# Sheet1.net
KiCad netlist of a schematic drawn in Altium Designer
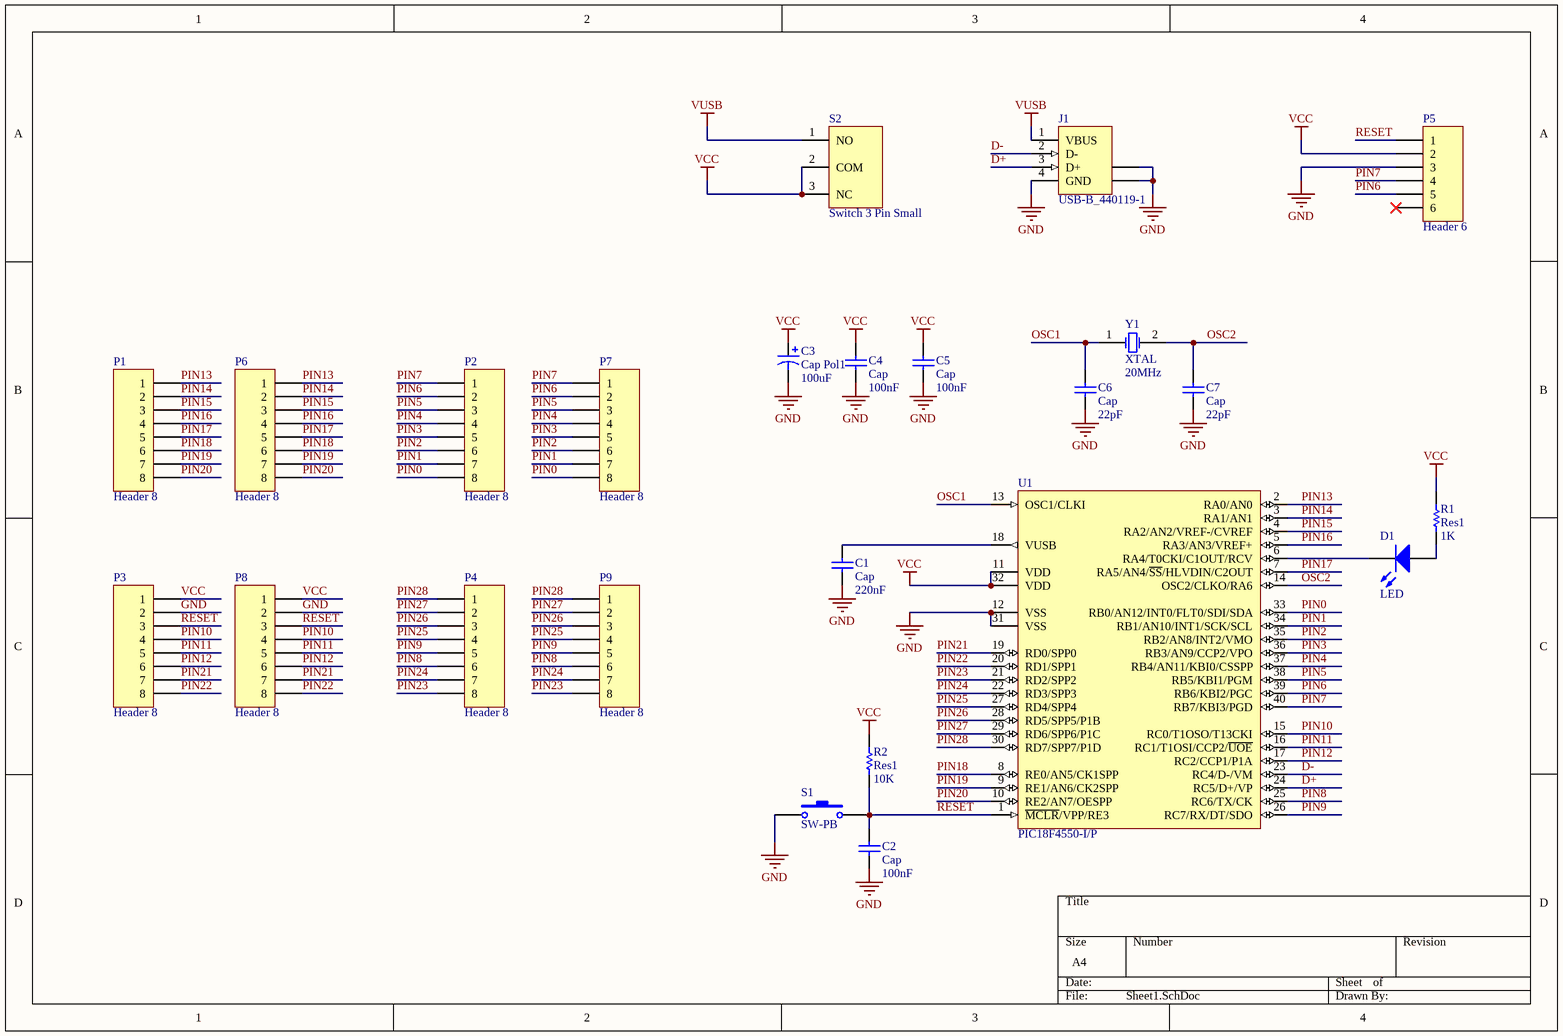
[diagram p0: Sheet1.SchDoc]

(export (version "E")
  (design (tool "Eeschema 10.0.6"))
  (components
    (comp (ref "C1")
      (value "Cap")
      (footprint "C1206")
      (description "Capacitor")
      (fields (field (name "ALTIUM_VALUE") "220nF") (field (name "PUBLISHER") "Altium Limited"))
      (libsource (lib "Miscellaneous Devices") (part "Cap"))
    )
    (comp (ref "C2")
      (value "Cap")
      (footprint "C1206")
      (description "Capacitor")
      (fields (field (name "ALTIUM_VALUE") "100nF") (field (name "PUBLISHER") "Altium Limited"))
      (libsource (lib "Miscellaneous Devices") (part "Cap"))
    )
    (comp (ref "C3")
      (value "Cap Pol1")
      (footprint "CAP1")
      (description "Polarized Capacitor (Radial)")
      (fields (field (name "ALTIUM_VALUE") "100uF") (field (name "PUBLISHER") "Altium Limited"))
      (libsource (lib "Miscellaneous Devices") (part "Cap Pol1"))
    )
    (comp (ref "C4")
      (value "Cap")
      (footprint "C1206")
      (description "Capacitor")
      (fields (field (name "ALTIUM_VALUE") "100nF") (field (name "PUBLISHER") "Altium Limited"))
      (libsource (lib "Miscellaneous Devices") (part "Cap"))
    )
    (comp (ref "C5")
      (value "Cap")
      (footprint "C1206")
      (description "Capacitor")
      (fields (field (name "ALTIUM_VALUE") "100nF") (field (name "PUBLISHER") "Altium Limited"))
      (libsource (lib "Miscellaneous Devices") (part "Cap"))
    )
    (comp (ref "C6")
      (value "Cap")
      (footprint "C1206")
      (description "Capacitor")
      (fields (field (name "ALTIUM_VALUE") "22pF") (field (name "PUBLISHER") "Altium Limited"))
      (libsource (lib "Miscellaneous Devices") (part "Cap"))
    )
    (comp (ref "C7")
      (value "Cap")
      (footprint "C1206")
      (description "Capacitor")
      (fields (field (name "ALTIUM_VALUE") "22pF") (field (name "PUBLISHER") "Altium Limited"))
      (libsource (lib "Miscellaneous Devices") (part "Cap"))
    )
    (comp (ref "D1")
      (value "LED")
      (footprint "LED0")
      (description "Typical RED GaAs LED")
      (fields (field (name "DESIGNER") "Meysam Parvizi") (field (name "EMAIL") "meysam.parvizi.ir@gmail.com"))
      (libsource (lib "mp") (part "LED"))
    )
    (comp (ref "J1")
      (value "USB-B_440119-1")
      (footprint "USB-B")
      (description "USB 1.1, Right Angle, Thru-Hole, B Type, Receptacle, 4 Position, Beige")
      (fields (field (name "PUBLISHER") "Altium Limited"))
      (libsource (lib "mp") (part "USB-B_440119-1"))
    )
    (comp (ref "P1")
      (value "Header 8")
      (footprint "HDR1X8")
      (description "Header, 8-Pin")
      (fields (field (name "PUBLISHER") "Altium Limited"))
      (libsource (lib "Miscellaneous Connectors") (part "Header 8"))
    )
    (comp (ref "P2")
      (value "Header 8")
      (footprint "HDR1X8")
      (description "Header, 8-Pin")
      (fields (field (name "PUBLISHER") "Altium Limited"))
      (libsource (lib "") (part "Header 8_1"))
    )
    (comp (ref "P3")
      (value "Header 8")
      (footprint "HDR1X8")
      (description "Header, 8-Pin")
      (fields (field (name "PUBLISHER") "Altium Limited"))
      (libsource (lib "Miscellaneous Connectors") (part "Header 8"))
    )
    (comp (ref "P4")
      (value "Header 8")
      (footprint "HDR1X8")
      (description "Header, 8-Pin")
      (fields (field (name "PUBLISHER") "Altium Limited"))
      (libsource (lib "") (part "Header 8_1"))
    )
    (comp (ref "P5")
      (value "Header 6")
      (footprint "HDR1X6")
      (description "Header, 6-Pin")
      (fields (field (name "PUBLISHER") "Altium Limited"))
      (libsource (lib "Miscellaneous Connectors") (part "Header 6"))
    )
    (comp (ref "P6")
      (value "Header 8")
      (footprint "HDR1X8")
      (description "Header, 8-Pin")
      (fields (field (name "PUBLISHER") "Altium Limited"))
      (libsource (lib "Miscellaneous Connectors") (part "Header 8"))
    )
    (comp (ref "P7")
      (value "Header 8")
      (footprint "HDR1X8")
      (description "Header, 8-Pin")
      (fields (field (name "PUBLISHER") "Altium Limited"))
      (libsource (lib "") (part "Header 8_1"))
    )
    (comp (ref "P8")
      (value "Header 8")
      (footprint "HDR1X8")
      (description "Header, 8-Pin")
      (fields (field (name "PUBLISHER") "Altium Limited"))
      (libsource (lib "Miscellaneous Connectors") (part "Header 8"))
    )
    (comp (ref "P9")
      (value "Header 8")
      (footprint "HDR1X8")
      (description "Header, 8-Pin")
      (fields (field (name "PUBLISHER") "Altium Limited"))
      (libsource (lib "") (part "Header 8_1"))
    )
    (comp (ref "R1")
      (value "Res1")
      (footprint "C1206")
      (description "Resistor")
      (fields (field (name "ALTIUM_VALUE") "1K") (field (name "PUBLISHER") "Altium Limited"))
      (libsource (lib "Miscellaneous Devices") (part "Res1"))
    )
    (comp (ref "R2")
      (value "Res1")
      (footprint "C1206")
      (description "Resistor")
      (fields (field (name "ALTIUM_VALUE") "10K") (field (name "PUBLISHER") "Altium Limited"))
      (libsource (lib "Miscellaneous Devices") (part "Res1"))
    )
    (comp (ref "S1")
      (value "SW-PB")
      (footprint "PUSH0")
      (description "Switch")
      (fields (field (name "PUBLISHER") "Altium Limited"))
      (libsource (lib "mp") (part "SW-PB"))
    )
    (comp (ref "S2")
      (value "Switch 3 Pin Small")
      (footprint "SW_ON_OFF_SMALL")
      (description "Switch 3 Pin")
      (fields (field (name "DESIGNER") "Meysam Parvizi") (field (name "EMAIL") "meysam.parvizi.ir@gmail.com"))
      (libsource (lib "mp") (part "Switch 3 Pin Small"))
    )
    (comp (ref "U1")
      (value "PIC18F4550-I/P")
      (footprint "PDIP600-P40")
      (fields (field (name "PUBLISHER") "Altium Limited"))
      (libsource (lib "Microchip Microcontroller 8-Bit PIC18") (part "PIC18F4550-I/P"))
    )
    (comp (ref "Y1")
      (value "XTAL")
      (footprint "XTAL")
      (description "Crystal Oscillator")
      (fields
        (field (name "ALTIUM_VALUE") "20MHz")
        (field (name "DESIGNER") "Meysam Parvizi")
        (field (name "EMAIL") "meysam.parvizi.ir@gmail.com")
      )
      (libsource (lib "mp") (part "XTAL"))
    )
  )
  (nets
    (net (code "1") (name "/D+") (class "Default")
      (node (ref "J1") (pin "3") (pinfunction "D+_3") (pintype "input"))
      (node (ref "U1") (pin "24") (pinfunction "RC5/D+/VP_24") (pintype "bidirectional"))
    )
    (net (code "2") (name "/D-") (class "Default")
      (node (ref "J1") (pin "2") (pinfunction "D-_2") (pintype "input"))
      (node (ref "U1") (pin "23") (pinfunction "RC4/D-/VM_23") (pintype "bidirectional"))
    )
    (net (code "3") (name "/OSC1") (class "Default")
      (node (ref "C6") (pin "2") (pinfunction "2_2") (pintype "passive"))
      (node (ref "U1") (pin "13") (pinfunction "OSC1/CLKI_13") (pintype "input"))
      (node (ref "Y1") (pin "1") (pinfunction "OSC1_1") (pintype "passive"))
    )
    (net (code "4") (name "/OSC2") (class "Default")
      (node (ref "C7") (pin "2") (pinfunction "2_2") (pintype "passive"))
      (node (ref "U1") (pin "14") (pinfunction "OSC2/CLKO/RA6_14") (pintype "bidirectional"))
      (node (ref "Y1") (pin "2") (pinfunction "OSC2_2") (pintype "passive"))
    )
    (net (code "5") (name "/PIN0") (class "Default")
      (node (ref "P2") (pin "8") (pinfunction "8_8") (pintype "passive"))
      (node (ref "P7") (pin "8") (pinfunction "8_8") (pintype "passive"))
      (node (ref "U1") (pin "33") (pinfunction "RB0/AN12/INT0/FLT0/SDI/SDA_33") (pintype "bidirectional"))
    )
    (net (code "6") (name "/PIN1") (class "Default")
      (node (ref "P2") (pin "7") (pinfunction "7_7") (pintype "passive"))
      (node (ref "P7") (pin "7") (pinfunction "7_7") (pintype "passive"))
      (node (ref "U1") (pin "34") (pinfunction "RB1/AN10/INT1/SCK/SCL_34") (pintype "bidirectional"))
    )
    (net (code "7") (name "/PIN2") (class "Default")
      (node (ref "P2") (pin "6") (pinfunction "6_6") (pintype "passive"))
      (node (ref "P7") (pin "6") (pinfunction "6_6") (pintype "passive"))
      (node (ref "U1") (pin "35") (pinfunction "RB2/AN8/INT2/VMO_35") (pintype "bidirectional"))
    )
    (net (code "8") (name "/PIN3") (class "Default")
      (node (ref "P2") (pin "5") (pinfunction "5_5") (pintype "passive"))
      (node (ref "P7") (pin "5") (pinfunction "5_5") (pintype "passive"))
      (node (ref "U1") (pin "36") (pinfunction "RB3/AN9/CCP2/VPO_36") (pintype "bidirectional"))
    )
    (net (code "9") (name "/PIN4") (class "Default")
      (node (ref "P2") (pin "4") (pinfunction "4_4") (pintype "passive"))
      (node (ref "P7") (pin "4") (pinfunction "4_4") (pintype "passive"))
      (node (ref "U1") (pin "37") (pinfunction "RB4/AN11/KBI0/CSSPP_37") (pintype "bidirectional"))
    )
    (net (code "10") (name "/PIN5") (class "Default")
      (node (ref "P2") (pin "3") (pinfunction "3_3") (pintype "passive"))
      (node (ref "P7") (pin "3") (pinfunction "3_3") (pintype "passive"))
      (node (ref "U1") (pin "38") (pinfunction "RB5/KBI1/PGM_38") (pintype "bidirectional"))
    )
    (net (code "11") (name "/PIN6") (class "Default")
      (node (ref "P2") (pin "2") (pinfunction "2_2") (pintype "passive"))
      (node (ref "P5") (pin "5") (pinfunction "5_5") (pintype "passive"))
      (node (ref "P7") (pin "2") (pinfunction "2_2") (pintype "passive"))
      (node (ref "U1") (pin "39") (pinfunction "RB6/KBI2/PGC_39") (pintype "bidirectional"))
    )
    (net (code "12") (name "/PIN7") (class "Default")
      (node (ref "P2") (pin "1") (pinfunction "1_1") (pintype "passive"))
      (node (ref "P5") (pin "4") (pinfunction "4_4") (pintype "passive"))
      (node (ref "P7") (pin "1") (pinfunction "1_1") (pintype "passive"))
      (node (ref "U1") (pin "40") (pinfunction "RB7/KBI3/PGD_40") (pintype "bidirectional"))
    )
    (net (code "13") (name "/PIN8") (class "Default")
      (node (ref "P4") (pin "6") (pinfunction "6_6") (pintype "passive"))
      (node (ref "P9") (pin "6") (pinfunction "6_6") (pintype "passive"))
      (node (ref "U1") (pin "25") (pinfunction "RC6/TX/CK_25") (pintype "bidirectional"))
    )
    (net (code "14") (name "/PIN9") (class "Default")
      (node (ref "P4") (pin "5") (pinfunction "5_5") (pintype "passive"))
      (node (ref "P9") (pin "5") (pinfunction "5_5") (pintype "passive"))
      (node (ref "U1") (pin "26") (pinfunction "RC7/RX/DT/SDO_26") (pintype "bidirectional"))
    )
    (net (code "15") (name "/PIN10") (class "Default")
      (node (ref "P3") (pin "4") (pinfunction "4_4") (pintype "passive"))
      (node (ref "P8") (pin "4") (pinfunction "4_4") (pintype "passive"))
      (node (ref "U1") (pin "15") (pinfunction "RC0/T1OSO/T13CKI_15") (pintype "bidirectional"))
    )
    (net (code "16") (name "/PIN11") (class "Default")
      (node (ref "P3") (pin "5") (pinfunction "5_5") (pintype "passive"))
      (node (ref "P8") (pin "5") (pinfunction "5_5") (pintype "passive"))
      (node (ref "U1") (pin "16") (pinfunction "RC1/T1OSI/CCP2/~{UOE}_16") (pintype "bidirectional"))
    )
    (net (code "17") (name "/PIN12") (class "Default")
      (node (ref "P3") (pin "6") (pinfunction "6_6") (pintype "passive"))
      (node (ref "P8") (pin "6") (pinfunction "6_6") (pintype "passive"))
      (node (ref "U1") (pin "17") (pinfunction "RC2/CCP1/P1A_17") (pintype "bidirectional"))
    )
    (net (code "18") (name "/PIN13") (class "Default")
      (node (ref "P1") (pin "1") (pinfunction "1_1") (pintype "passive"))
      (node (ref "P6") (pin "1") (pinfunction "1_1") (pintype "passive"))
      (node (ref "U1") (pin "2") (pinfunction "RA0/AN0_2") (pintype "bidirectional"))
    )
    (net (code "19") (name "/PIN14") (class "Default")
      (node (ref "P1") (pin "2") (pinfunction "2_2") (pintype "passive"))
      (node (ref "P6") (pin "2") (pinfunction "2_2") (pintype "passive"))
      (node (ref "U1") (pin "3") (pinfunction "RA1/AN1_3") (pintype "bidirectional"))
    )
    (net (code "20") (name "/PIN15") (class "Default")
      (node (ref "P1") (pin "3") (pinfunction "3_3") (pintype "passive"))
      (node (ref "P6") (pin "3") (pinfunction "3_3") (pintype "passive"))
      (node (ref "U1") (pin "4") (pinfunction "RA2/AN2/VREF-/CVREF_4") (pintype "bidirectional"))
    )
    (net (code "21") (name "/PIN16") (class "Default")
      (node (ref "P1") (pin "4") (pinfunction "4_4") (pintype "passive"))
      (node (ref "P6") (pin "4") (pinfunction "4_4") (pintype "passive"))
      (node (ref "U1") (pin "5") (pinfunction "RA3/AN3/VREF+_5") (pintype "bidirectional"))
    )
    (net (code "22") (name "/PIN17") (class "Default")
      (node (ref "P1") (pin "5") (pinfunction "5_5") (pintype "passive"))
      (node (ref "P6") (pin "5") (pinfunction "5_5") (pintype "passive"))
      (node (ref "U1") (pin "7") (pinfunction "RA5/AN4/~{SS}/HLVDIN/C2OUT_7") (pintype "bidirectional"))
    )
    (net (code "23") (name "/PIN18") (class "Default")
      (node (ref "P1") (pin "6") (pinfunction "6_6") (pintype "passive"))
      (node (ref "P6") (pin "6") (pinfunction "6_6") (pintype "passive"))
      (node (ref "U1") (pin "8") (pinfunction "RE0/AN5/CK1SPP_8") (pintype "bidirectional"))
    )
    (net (code "24") (name "/PIN19") (class "Default")
      (node (ref "P1") (pin "7") (pinfunction "7_7") (pintype "passive"))
      (node (ref "P6") (pin "7") (pinfunction "7_7") (pintype "passive"))
      (node (ref "U1") (pin "9") (pinfunction "RE1/AN6/CK2SPP_9") (pintype "bidirectional"))
    )
    (net (code "25") (name "/PIN20") (class "Default")
      (node (ref "P1") (pin "8") (pinfunction "8_8") (pintype "passive"))
      (node (ref "P6") (pin "8") (pinfunction "8_8") (pintype "passive"))
      (node (ref "U1") (pin "10") (pinfunction "RE2/AN7/OESPP_10") (pintype "bidirectional"))
    )
    (net (code "26") (name "/PIN21") (class "Default")
      (node (ref "P3") (pin "7") (pinfunction "7_7") (pintype "passive"))
      (node (ref "P8") (pin "7") (pinfunction "7_7") (pintype "passive"))
      (node (ref "U1") (pin "19") (pinfunction "RD0/SPP0_19") (pintype "bidirectional"))
    )
    (net (code "27") (name "/PIN22") (class "Default")
      (node (ref "P3") (pin "8") (pinfunction "8_8") (pintype "passive"))
      (node (ref "P8") (pin "8") (pinfunction "8_8") (pintype "passive"))
      (node (ref "U1") (pin "20") (pinfunction "RD1/SPP1_20") (pintype "bidirectional"))
    )
    (net (code "28") (name "/PIN23") (class "Default")
      (node (ref "P4") (pin "8") (pinfunction "8_8") (pintype "passive"))
      (node (ref "P9") (pin "8") (pinfunction "8_8") (pintype "passive"))
      (node (ref "U1") (pin "21") (pinfunction "RD2/SPP2_21") (pintype "bidirectional"))
    )
    (net (code "29") (name "/PIN24") (class "Default")
      (node (ref "P4") (pin "7") (pinfunction "7_7") (pintype "passive"))
      (node (ref "P9") (pin "7") (pinfunction "7_7") (pintype "passive"))
      (node (ref "U1") (pin "22") (pinfunction "RD3/SPP3_22") (pintype "bidirectional"))
    )
    (net (code "30") (name "/PIN25") (class "Default")
      (node (ref "P4") (pin "4") (pinfunction "4_4") (pintype "passive"))
      (node (ref "P9") (pin "4") (pinfunction "4_4") (pintype "passive"))
      (node (ref "U1") (pin "27") (pinfunction "RD4/SPP4_27") (pintype "bidirectional"))
    )
    (net (code "31") (name "/PIN26") (class "Default")
      (node (ref "P4") (pin "3") (pinfunction "3_3") (pintype "passive"))
      (node (ref "P9") (pin "3") (pinfunction "3_3") (pintype "passive"))
      (node (ref "U1") (pin "28") (pinfunction "RD5/SPP5/P1B_28") (pintype "bidirectional"))
    )
    (net (code "32") (name "/PIN27") (class "Default")
      (node (ref "P4") (pin "2") (pinfunction "2_2") (pintype "passive"))
      (node (ref "P9") (pin "2") (pinfunction "2_2") (pintype "passive"))
      (node (ref "U1") (pin "29") (pinfunction "RD6/SPP6/P1C_29") (pintype "bidirectional"))
    )
    (net (code "33") (name "/PIN28") (class "Default")
      (node (ref "P4") (pin "1") (pinfunction "1_1") (pintype "passive"))
      (node (ref "P9") (pin "1") (pinfunction "1_1") (pintype "passive"))
      (node (ref "U1") (pin "30") (pinfunction "RD7/SPP7/P1D_30") (pintype "bidirectional"))
    )
    (net (code "34") (name "/RESET") (class "Default")
      (node (ref "C2") (pin "2") (pinfunction "2_2") (pintype "passive"))
      (node (ref "P3") (pin "3") (pinfunction "3_3") (pintype "passive"))
      (node (ref "P5") (pin "1") (pinfunction "1_1") (pintype "passive"))
      (node (ref "P8") (pin "3") (pinfunction "3_3") (pintype "passive"))
      (node (ref "R2") (pin "1") (pinfunction "1_1") (pintype "passive"))
      (node (ref "S1") (pin "2") (pinfunction "2_2") (pintype "passive"))
      (node (ref "U1") (pin "1") (pinfunction "~{MCLR}/VPP/RE3_1") (pintype "input"))
    )
    (net (code "35") (name "GND") (class "Default")
      (node (ref "C1") (pin "1") (pinfunction "1_1") (pintype "passive"))
      (node (ref "C2") (pin "1") (pinfunction "1_1") (pintype "passive"))
      (node (ref "C3") (pin "2") (pinfunction "2_2") (pintype "passive"))
      (node (ref "C4") (pin "1") (pinfunction "1_1") (pintype "passive"))
      (node (ref "C5") (pin "1") (pinfunction "1_1") (pintype "passive"))
      (node (ref "C6") (pin "1") (pinfunction "1_1") (pintype "passive"))
      (node (ref "C7") (pin "1") (pinfunction "1_1") (pintype "passive"))
      (node (ref "J1") (pin "4") (pinfunction "GND_4") (pintype "power_in"))
      (node (ref "J1") (pin "5") (pinfunction "SHLD_5") (pintype "passive"))
      (node (ref "J1") (pin "6") (pinfunction "SHLD_6") (pintype "passive"))
      (node (ref "P3") (pin "2") (pinfunction "2_2") (pintype "passive"))
      (node (ref "P5") (pin "3") (pinfunction "3_3") (pintype "passive"))
      (node (ref "P8") (pin "2") (pinfunction "2_2") (pintype "passive"))
      (node (ref "S1") (pin "1") (pinfunction "1_1") (pintype "passive"))
      (node (ref "U1") (pin "12") (pinfunction "VSS_12") (pintype "power_in"))
      (node (ref "U1") (pin "31") (pinfunction "VSS_31") (pintype "power_in"))
    )
    (net (code "36") (name "Net-(D1-A)") (class "Default")
      (node (ref "D1") (pin "1") (pinfunction "A_1") (pintype "passive"))
      (node (ref "R1") (pin "1") (pinfunction "1_1") (pintype "passive"))
    )
    (net (code "37") (name "Net-(D1-K)") (class "Default")
      (node (ref "D1") (pin "2") (pinfunction "K_2") (pintype "passive"))
      (node (ref "U1") (pin "6") (pinfunction "RA4/T0CKI/C1OUT/RCV_6") (pintype "bidirectional"))
    )
    (net (code "38") (name "Net-(U1-VUSB)") (class "Default")
      (node (ref "C1") (pin "2") (pinfunction "2_2") (pintype "passive"))
      (node (ref "U1") (pin "18") (pinfunction "VUSB_18") (pintype "output"))
    )
    (net (code "39") (name "VCC") (class "Default")
      (node (ref "C3") (pin "1") (pinfunction "1_1") (pintype "passive"))
      (node (ref "C4") (pin "2") (pinfunction "2_2") (pintype "passive"))
      (node (ref "C5") (pin "2") (pinfunction "2_2") (pintype "passive"))
      (node (ref "P3") (pin "1") (pinfunction "1_1") (pintype "passive"))
      (node (ref "P5") (pin "2") (pinfunction "2_2") (pintype "passive"))
      (node (ref "P8") (pin "1") (pinfunction "1_1") (pintype "passive"))
      (node (ref "R1") (pin "2") (pinfunction "2_2") (pintype "passive"))
      (node (ref "R2") (pin "2") (pinfunction "2_2") (pintype "passive"))
      (node (ref "S2") (pin "2") (pinfunction "COM_2") (pintype "power_in"))
      (node (ref "S2") (pin "3") (pinfunction "NC_3") (pintype "passive"))
      (node (ref "U1") (pin "11") (pinfunction "VDD_11") (pintype "power_in"))
      (node (ref "U1") (pin "32") (pinfunction "VDD_32") (pintype "power_in"))
    )
    (net (code "40") (name "VUSB") (class "Default")
      (node (ref "J1") (pin "1") (pinfunction "VBUS_1") (pintype "power_in"))
      (node (ref "S2") (pin "1") (pinfunction "NO_1") (pintype "passive"))
    )
    (net (code "41") (name "unconnected-(P5-Pad6)") (class "Default")
      (node (ref "P5") (pin "6") (pinfunction "6_6") (pintype "passive+no_connect"))
    )
  )
)
